# Main.net
KiCad netlist of a schematic drawn in EAGLE
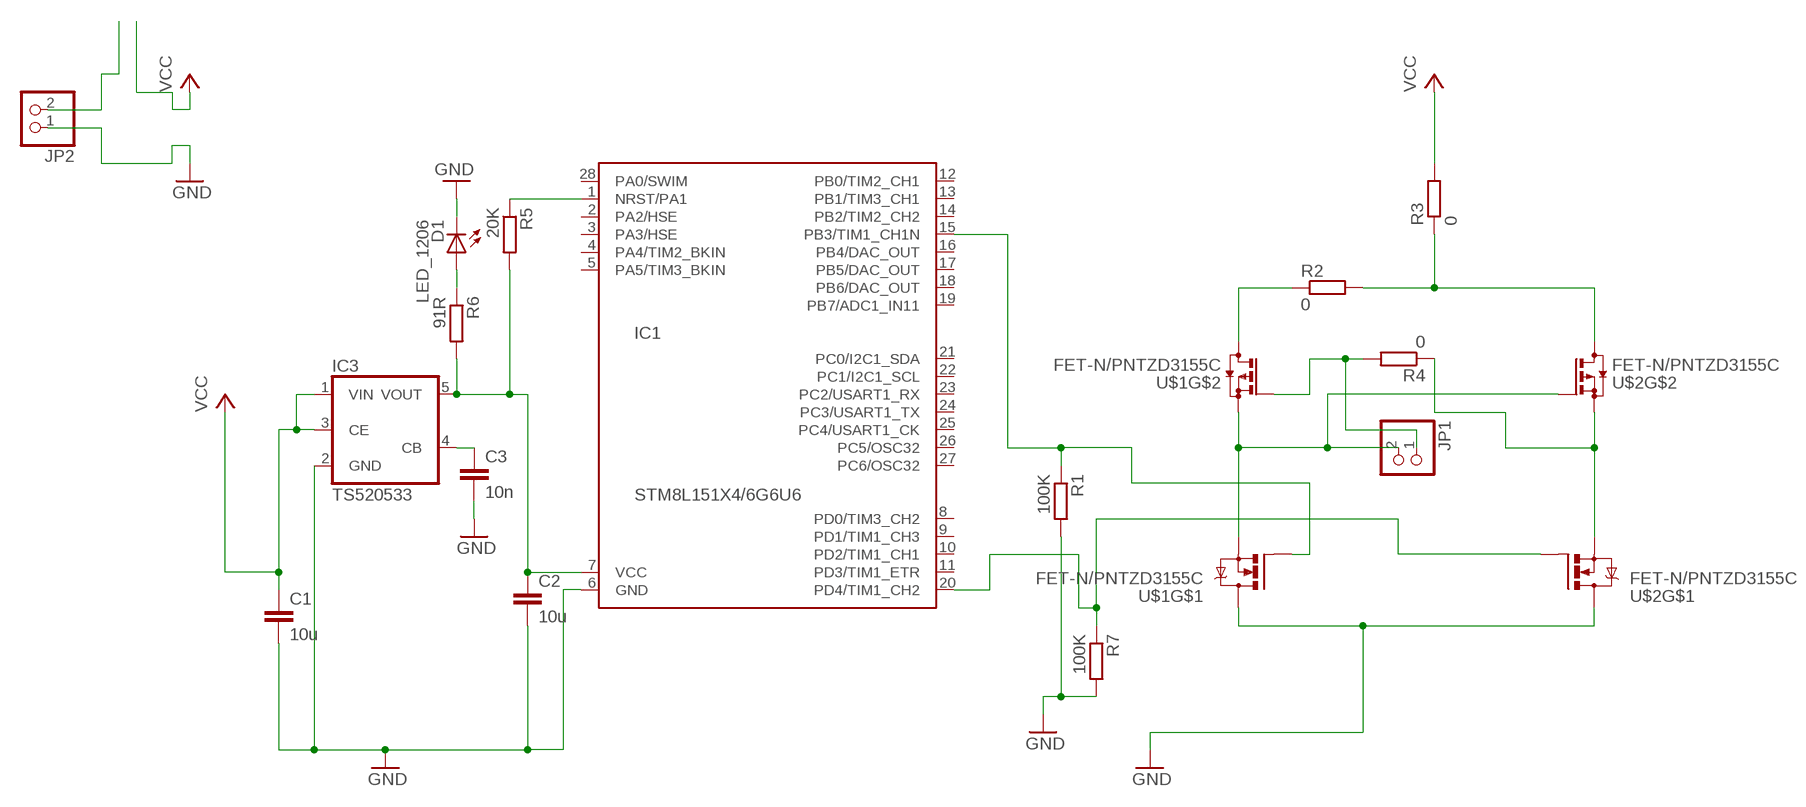
[diagram p0: schematic, sheet 1]

(export (version "E")
  (design (tool "Eeschema 10.0.6"))
  (components
    (comp (ref "C1")
      (value "10u")
      (footprint "eagle-import:C0805")
      (libsource (lib "eagle-import") (part "C-EUC0805"))
    )
    (comp (ref "C2")
      (value "10u")
      (footprint "eagle-import:C0805")
      (libsource (lib "eagle-import") (part "C-EUC0805"))
    )
    (comp (ref "C3")
      (value "10n")
      (footprint "eagle-import:C0805")
      (libsource (lib "eagle-import") (part "C-EUC0805"))
    )
    (comp (ref "D1")
      (value "LED_1206")
      (footprint "eagle-import:LED1206")
      (libsource (lib "eagle-import") (part "LED_1206"))
    )
    (comp (ref "IC1")
      (value "STM8L151X4/6G6U6")
      (footprint "eagle-import:QFN28")
      (libsource (lib "eagle-import") (part "STM8L151X4/6G6U6"))
    )
    (comp (ref "IC3")
      (value "TS520533")
      (footprint "eagle-import:SOT25")
      (libsource (lib "eagle-import") (part "TS520533"))
    )
    (comp (ref "JP1")
      (value "PINHD-1X2")
      (footprint "eagle-import:1X02")
      (libsource (lib "eagle-import") (part "PINHD-1X2"))
    )
    (comp (ref "JP2")
      (value "PINHD-1X2")
      (footprint "eagle-import:1X02")
      (libsource (lib "eagle-import") (part "PINHD-1X2"))
    )
    (comp (ref "R1")
      (value "100K")
      (footprint "eagle-import:R0805")
      (libsource (lib "eagle-import") (part "R_0805"))
    )
    (comp (ref "R2")
      (value "0")
      (footprint "eagle-import:R0805")
      (libsource (lib "eagle-import") (part "R_0805"))
    )
    (comp (ref "R3")
      (value "0")
      (footprint "eagle-import:R0805")
      (libsource (lib "eagle-import") (part "R_0805"))
    )
    (comp (ref "R4")
      (value "0")
      (footprint "eagle-import:R0805")
      (libsource (lib "eagle-import") (part "R_0805"))
    )
    (comp (ref "R5")
      (value "20K")
      (footprint "eagle-import:R0805")
      (libsource (lib "eagle-import") (part "R_0805"))
    )
    (comp (ref "R6")
      (value "91R")
      (footprint "eagle-import:R0805")
      (libsource (lib "eagle-import") (part "R_0805"))
    )
    (comp (ref "R7")
      (value "100K")
      (footprint "eagle-import:R0805")
      (libsource (lib "eagle-import") (part "R_0805"))
    )
    (comp (ref "U$1")
      (value "FET-N/PNTZD3155C")
      (footprint "eagle-import:SOT-563")
      (libsource (lib "eagle-import") (part "FET-N/PNTZD3155C"))
    )
    (comp (ref "U$2")
      (value "FET-N/PNTZD3155C")
      (footprint "eagle-import:SOT-563")
      (libsource (lib "eagle-import") (part "FET-N/PNTZD3155C"))
    )
  )
  (nets
    (net (code "1") (name "GND") (class "Default")
      (node (ref "C1") (pin "2") (pinfunction "2_2") (pintype "passive"))
      (node (ref "C2") (pin "2") (pinfunction "2_2") (pintype "passive"))
      (node (ref "C3") (pin "2") (pinfunction "2_2") (pintype "passive"))
      (node (ref "D1") (pin "C") (pinfunction "C_C") (pintype "passive"))
      (node (ref "IC1") (pin "6") (pinfunction "GND_6") (pintype "power_in"))
      (node (ref "IC3") (pin "2") (pinfunction "GND_2") (pintype "passive"))
      (node (ref "JP2") (pin "1") (pinfunction "1_1") (pintype "passive"))
      (node (ref "R1") (pin "2") (pinfunction "2_2") (pintype "passive"))
      (node (ref "R7") (pin "2") (pinfunction "2_2") (pintype "passive"))
      (node (ref "U$1") (pin "6") (pinfunction "D_6") (pintype "passive"))
      (node (ref "U$2") (pin "6") (pinfunction "D_6") (pintype "passive"))
    )
    (net (code "2") (name "Net-(D1-PadA)") (class "Default")
      (node (ref "D1") (pin "A") (pinfunction "A_A") (pintype "passive"))
      (node (ref "R6") (pin "1") (pinfunction "1_1") (pintype "passive"))
    )
    (net (code "3") (name "Net-(IC1-NRST{slash}PA1)") (class "Default")
      (node (ref "IC1") (pin "1") (pinfunction "NRST/PA1_1") (pintype "bidirectional"))
      (node (ref "R5") (pin "1") (pinfunction "1_1") (pintype "passive"))
    )
    (net (code "4") (name "Net-(IC1-PB3{slash}TIM1_CH1N)") (class "Default")
      (node (ref "IC1") (pin "15") (pinfunction "PB3/TIM1_CH1N_15") (pintype "bidirectional"))
      (node (ref "R1") (pin "1") (pinfunction "1_1") (pintype "passive"))
      (node (ref "U$1") (pin "2") (pinfunction "G_2") (pintype "passive"))
    )
    (net (code "5") (name "Net-(IC1-PD4{slash}TIM1_CH2)") (class "Default")
      (node (ref "IC1") (pin "20") (pinfunction "PD4/TIM1_CH2_20") (pintype "bidirectional"))
      (node (ref "R7") (pin "1") (pinfunction "1_1") (pintype "passive"))
      (node (ref "U$2") (pin "2") (pinfunction "G_2") (pintype "passive"))
    )
    (net (code "6") (name "Net-(IC1-VCC)") (class "Default")
      (node (ref "C2") (pin "1") (pinfunction "1_1") (pintype "passive"))
      (node (ref "IC1") (pin "7") (pinfunction "VCC_7") (pintype "power_in"))
      (node (ref "IC3") (pin "5") (pinfunction "VOUT_5") (pintype "passive"))
      (node (ref "R5") (pin "2") (pinfunction "2_2") (pintype "passive"))
      (node (ref "R6") (pin "2") (pinfunction "2_2") (pintype "passive"))
    )
    (net (code "7") (name "Net-(IC3-CB)") (class "Default")
      (node (ref "C3") (pin "1") (pinfunction "1_1") (pintype "passive"))
      (node (ref "IC3") (pin "4") (pinfunction "CB_4") (pintype "input"))
    )
    (net (code "8") (name "Net-(U$1A-S)") (class "Default")
      (node (ref "JP1") (pin "2") (pinfunction "2_2") (pintype "passive"))
      (node (ref "U$1") (pin "1") (pinfunction "S_1") (pintype "passive"))
      (node (ref "U$1") (pin "4") (pinfunction "S_4") (pintype "passive"))
      (node (ref "U$2") (pin "5") (pinfunction "G_5") (pintype "passive"))
    )
    (net (code "9") (name "Net-(U$1B-D)") (class "Default")
      (node (ref "R2") (pin "1") (pinfunction "1_1") (pintype "passive"))
      (node (ref "U$1") (pin "3") (pinfunction "D_3") (pintype "passive"))
    )
    (net (code "10") (name "Net-(U$1B-G)") (class "Default")
      (node (ref "JP1") (pin "1") (pinfunction "1_1") (pintype "passive"))
      (node (ref "R4") (pin "2") (pinfunction "2_2") (pintype "passive"))
      (node (ref "U$1") (pin "5") (pinfunction "G_5") (pintype "passive"))
    )
    (net (code "11") (name "Net-(U$2A-S)") (class "Default")
      (node (ref "R4") (pin "1") (pinfunction "1_1") (pintype "passive"))
      (node (ref "U$2") (pin "1") (pinfunction "S_1") (pintype "passive"))
      (node (ref "U$2") (pin "4") (pinfunction "S_4") (pintype "passive"))
    )
    (net (code "12") (name "Net-(U$2B-D)") (class "Default")
      (node (ref "R2") (pin "2") (pinfunction "2_2") (pintype "passive"))
      (node (ref "R3") (pin "1") (pinfunction "1_1") (pintype "passive"))
      (node (ref "U$2") (pin "3") (pinfunction "D_3") (pintype "passive"))
    )
    (net (code "13") (name "VCC") (class "Default")
      (node (ref "C1") (pin "1") (pinfunction "1_1") (pintype "passive"))
      (node (ref "IC3") (pin "1") (pinfunction "VIN_1") (pintype "input"))
      (node (ref "IC3") (pin "3") (pinfunction "CE_3") (pintype "input"))
      (node (ref "R3") (pin "2") (pinfunction "2_2") (pintype "passive"))
    )
    (net (code "14") (name "unconnected-(IC1-PA0{slash}SWIM-Pad28)") (class "Default")
      (node (ref "IC1") (pin "28") (pinfunction "PA0/SWIM_28") (pintype "bidirectional"))
    )
    (net (code "15") (name "unconnected-(IC1-PA2{slash}HSE-Pad2)") (class "Default")
      (node (ref "IC1") (pin "2") (pinfunction "PA2/HSE_2") (pintype "bidirectional"))
    )
    (net (code "16") (name "unconnected-(IC1-PA3{slash}HSE-Pad3)") (class "Default")
      (node (ref "IC1") (pin "3") (pinfunction "PA3/HSE_3") (pintype "bidirectional"))
    )
    (net (code "17") (name "unconnected-(IC1-PA4{slash}TIM2_BKIN-Pad4)") (class "Default")
      (node (ref "IC1") (pin "4") (pinfunction "PA4/TIM2_BKIN_4") (pintype "bidirectional"))
    )
    (net (code "18") (name "unconnected-(IC1-PA5{slash}TIM3_BKIN-Pad5)") (class "Default")
      (node (ref "IC1") (pin "5") (pinfunction "PA5/TIM3_BKIN_5") (pintype "bidirectional"))
    )
    (net (code "19") (name "unconnected-(IC1-PB0{slash}TIM2_CH1-Pad12)") (class "Default")
      (node (ref "IC1") (pin "12") (pinfunction "PB0/TIM2_CH1_12") (pintype "bidirectional"))
    )
    (net (code "20") (name "unconnected-(IC1-PB1{slash}TIM3_CH1-Pad13)") (class "Default")
      (node (ref "IC1") (pin "13") (pinfunction "PB1/TIM3_CH1_13") (pintype "bidirectional"))
    )
    (net (code "21") (name "unconnected-(IC1-PB2{slash}TIM2_CH2-Pad14)") (class "Default")
      (node (ref "IC1") (pin "14") (pinfunction "PB2/TIM2_CH2_14") (pintype "bidirectional"))
    )
    (net (code "22") (name "unconnected-(IC1-PB4{slash}DAC_OUT-Pad16)") (class "Default")
      (node (ref "IC1") (pin "16") (pinfunction "PB4/DAC_OUT_16") (pintype "bidirectional"))
    )
    (net (code "23") (name "unconnected-(IC1-PB5{slash}DAC_OUT-Pad17)") (class "Default")
      (node (ref "IC1") (pin "17") (pinfunction "PB5/DAC_OUT_17") (pintype "bidirectional"))
    )
    (net (code "24") (name "unconnected-(IC1-PB6{slash}DAC_OUT-Pad18)") (class "Default")
      (node (ref "IC1") (pin "18") (pinfunction "PB6/DAC_OUT_18") (pintype "bidirectional"))
    )
    (net (code "25") (name "unconnected-(IC1-PB7{slash}ADC1_IN11-Pad19)") (class "Default")
      (node (ref "IC1") (pin "19") (pinfunction "PB7/ADC1_IN11_19") (pintype "bidirectional"))
    )
    (net (code "26") (name "unconnected-(IC1-PC0{slash}I2C1_SDA-Pad21)") (class "Default")
      (node (ref "IC1") (pin "21") (pinfunction "PC0/I2C1_SDA_21") (pintype "bidirectional"))
    )
    (net (code "27") (name "unconnected-(IC1-PC1{slash}I2C1_SCL-Pad22)") (class "Default")
      (node (ref "IC1") (pin "22") (pinfunction "PC1/I2C1_SCL_22") (pintype "bidirectional"))
    )
    (net (code "28") (name "unconnected-(IC1-PC2{slash}USART1_RX-Pad23)") (class "Default")
      (node (ref "IC1") (pin "23") (pinfunction "PC2/USART1_RX_23") (pintype "bidirectional"))
    )
    (net (code "29") (name "unconnected-(IC1-PC3{slash}USART1_TX-Pad24)") (class "Default")
      (node (ref "IC1") (pin "24") (pinfunction "PC3/USART1_TX_24") (pintype "bidirectional"))
    )
    (net (code "30") (name "unconnected-(IC1-PC4{slash}USART1_CK-Pad25)") (class "Default")
      (node (ref "IC1") (pin "25") (pinfunction "PC4/USART1_CK_25") (pintype "bidirectional"))
    )
    (net (code "31") (name "unconnected-(IC1-PC5{slash}OSC32-Pad26)") (class "Default")
      (node (ref "IC1") (pin "26") (pinfunction "PC5/OSC32_26") (pintype "bidirectional"))
    )
    (net (code "32") (name "unconnected-(IC1-PC6{slash}OSC32-Pad27)") (class "Default")
      (node (ref "IC1") (pin "27") (pinfunction "PC6/OSC32_27") (pintype "bidirectional"))
    )
    (net (code "33") (name "unconnected-(IC1-PD0{slash}TIM3_CH2-Pad8)") (class "Default")
      (node (ref "IC1") (pin "8") (pinfunction "PD0/TIM3_CH2_8") (pintype "bidirectional"))
    )
    (net (code "34") (name "unconnected-(IC1-PD1{slash}TIM1_CH3-Pad9)") (class "Default")
      (node (ref "IC1") (pin "9") (pinfunction "PD1/TIM1_CH3_9") (pintype "bidirectional"))
    )
    (net (code "35") (name "unconnected-(IC1-PD2{slash}TIM1_CH1-Pad10)") (class "Default")
      (node (ref "IC1") (pin "10") (pinfunction "PD2/TIM1_CH1_10") (pintype "bidirectional"))
    )
    (net (code "36") (name "unconnected-(IC1-PD3{slash}TIM1_ETR-Pad11)") (class "Default")
      (node (ref "IC1") (pin "11") (pinfunction "PD3/TIM1_ETR_11") (pintype "bidirectional"))
    )
    (net (code "37") (name "unconnected-(JP2-Pad2)") (class "Default")
      (node (ref "JP2") (pin "2") (pinfunction "2_2") (pintype "passive"))
    )
  )
)
